# 3_3V_to_1_0V.net
KiCad netlist of a schematic drawn in Altium Designer
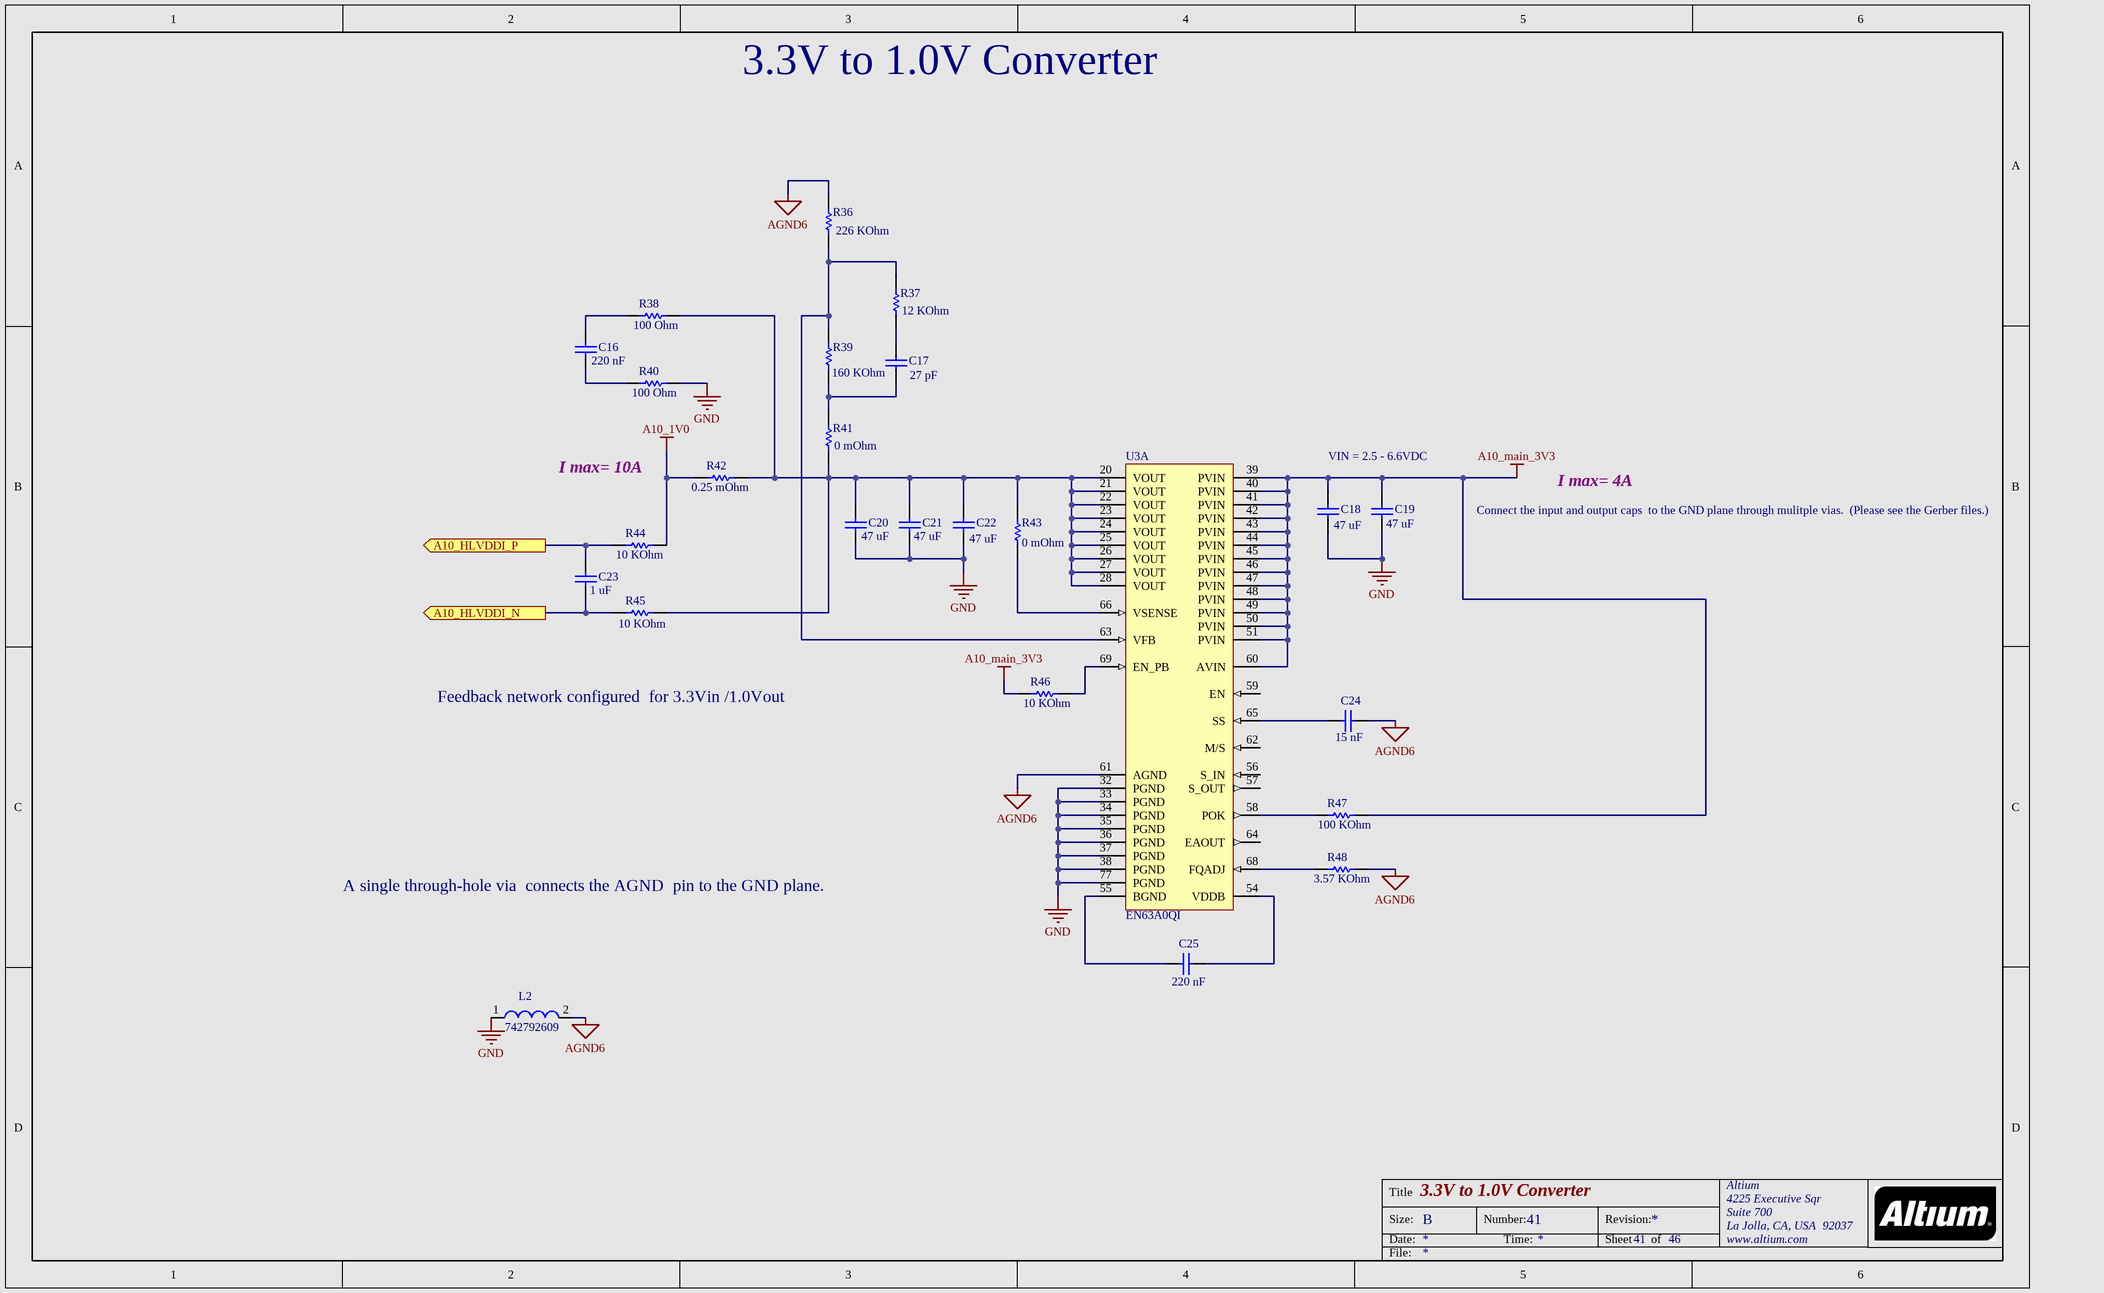
[diagram p0: 3.3V_to_1.0V.SchDoc]

(export (version "E")
  (design (tool "Eeschema 10.0.6"))
  (components
    (comp (ref "C16")
      (value "GRM155R61A224KE19D")
      (footprint "CAPC1005X55X25NL05T10")
      (description "Chip Capacitor, 220 nF, +/- 10%, 10 V, -55 to 85 degC, 0402 (1005 Metric), RoHS, Tape and Reel")
      (fields
        (field (name "TOLERANCE") "10%")
        (field (name "CAPACITANCE") "220 nF")
        (field (name "MANUFACTURER") "Basic Passives")
      )
      (libsource (lib "Altium Content Vault") (part "CAP-NP-2"))
    )
    (comp (ref "C17")
      (value "ECJ-0EC1H270J")
      (footprint "CAPC1005X55X20ML5T10")
      (description "Chip Capacitor, 27 pF, +/- 5%, 50 V, -55 to 125 degC, 0402 (1005 Metric), RoHS, Tape and Reel")
      (fields (field (name "TOLERANCE") "5%") (field (name "CAPACITANCE") "27 pF"))
      (libsource (lib "Altium Content Vault") (part "CMP-1665-00021-1"))
    )
    (comp (ref "C18")
      (value "C3216X5R1A476M160AB")
      (footprint "CAPC3216X180X20ML20")
      (description "Chip Capacitor, 47 uF, +/- 20%, 10 V, -55 to 85 degC, 1206 (3216 Metric), RoHS, Tape and Reel")
      (fields (field (name "TOLERANCE") "20%") (field (name "CAPACITANCE") "47 uF"))
      (libsource (lib "") (part "CAP-NP-2_1"))
    )
    (comp (ref "C19")
      (value "C3216X5R1A476M160AB")
      (footprint "CAPC3216X180X20ML20")
      (description "Chip Capacitor, 47 uF, +/- 20%, 10 V, -55 to 85 degC, 1206 (3216 Metric), RoHS, Tape and Reel")
      (fields (field (name "TOLERANCE") "20%") (field (name "CAPACITANCE") "47 uF"))
      (libsource (lib "") (part "CAP-NP-2_1"))
    )
    (comp (ref "C20")
      (value "C3216X5R1A476M160AB")
      (footprint "CAPC3216X180X20ML20")
      (description "Chip Capacitor, 47 uF, +/- 20%, 10 V, -55 to 85 degC, 1206 (3216 Metric), RoHS, Tape and Reel")
      (fields (field (name "TOLERANCE") "20%") (field (name "CAPACITANCE") "47 uF"))
      (libsource (lib "") (part "CAP-NP-2_1"))
    )
    (comp (ref "C21")
      (value "C3216X5R1A476M160AB")
      (footprint "CAPC3216X180X20ML20")
      (description "Chip Capacitor, 47 uF, +/- 20%, 10 V, -55 to 85 degC, 1206 (3216 Metric), RoHS, Tape and Reel")
      (fields (field (name "TOLERANCE") "20%") (field (name "CAPACITANCE") "47 uF"))
      (libsource (lib "") (part "CAP-NP-2_1"))
    )
    (comp (ref "C22")
      (value "C3216X5R1A476M160AB")
      (footprint "CAPC3216X180X20ML20")
      (description "Chip Capacitor, 47 uF, +/- 20%, 10 V, -55 to 85 degC, 1206 (3216 Metric), RoHS, Tape and Reel")
      (fields (field (name "TOLERANCE") "20%") (field (name "CAPACITANCE") "47 uF"))
      (libsource (lib "") (part "CAP-NP-2_1"))
    )
    (comp (ref "C23")
      (value "CGB2A1X5R1E105K033BC")
      (footprint "CAPC1005X33X10LL5")
      (description "Chip Capacitor, 1 uF, +/- 10%, 25 V, -55 to 85 degC, 0402 (1005 Metric), RoHS, Tape and Reel")
      (fields (field (name "TOLERANCE") "10%") (field (name "CAPACITANCE") "1 uF"))
      (libsource (lib "") (part "CAP-NP-2_1"))
    )
    (comp (ref "C24")
      (value "VJ0402Y153JXQPW1BC")
      (footprint "CAPC1005X55X23ML05T8")
      (description "Chip Capacitor, 15 nF, +/- 5%, 10 V, -55 to 125 degC, 0402 (1005 Metric), RoHS, Tape and Reel")
      (fields (field (name "CAPACITANCE") "15 nF") (field (name "TOLERANCE") "5%"))
      (libsource (lib "Altium Content Vault") (part "CAP-NP-2"))
    )
    (comp (ref "C25")
      (value "GRM155R61A224KE19D")
      (footprint "CAPC1005X55X25NL05T10")
      (description "Chip Capacitor, 220 nF, +/- 10%, 10 V, -55 to 85 degC, 0402 (1005 Metric), RoHS, Tape and Reel")
      (fields
        (field (name "TOLERANCE") "10%")
        (field (name "CAPACITANCE") "220 nF")
        (field (name "MANUFACTURER") "Basic Passives")
      )
      (libsource (lib "Altium Content Vault") (part "CAP-NP-2"))
    )
    (comp (ref "L2")
      (value "742792609")
      (footprint "SMD-0603")
      (description "SMD EMI Suppression Ferrite Bead WE-CBF, Z = 30 Ohm")
      (libsource (lib "Altium Content Vault") (part "CMP-0220-00193-1"))
    )
    (comp (ref "R36")
      (value "ERJ-2RKF2263X")
      (footprint "RESC1005X40X25NL05T05")
      (description "Chip Resistor, 226 KOhm, +/- 1%, 100 mW, -55 to 155 degC, 0402 (1005 Metric), RoHS, Tape and Reel")
      (fields
        (field (name "RESISTANCE") "226 KOhm")
        (field (name "TOLERANCE") "1%")
        (field (name "MANUFACTURER") "Basic Passives")
      )
      (libsource (lib "Altium Content Vault") (part "RES-2"))
    )
    (comp (ref "R37")
      (value "ERJ-2RKF1202X")
      (footprint "RESC1005X40X25ML05T05")
      (description "Chip Resistor, 12 KOhm, +/- 1%, 0.1 W, -55 to 155 degC, 0402 (1005 Metric), RoHS, Tape and Reel")
      (fields (field (name "RESISTANCE") "12 KOhm") (field (name "TOLERANCE") "1%"))
      (libsource (lib "Altium Content Vault") (part "RES-2"))
    )
    (comp (ref "R38")
      (value "ERJ-2RKF1000X")
      (footprint "RESC1005X40X25LL05T05")
      (description "Chip Resistor, 100 Ohm, +/- 1%, 100 mW, -55 to 155 degC, 0402 (1005 Metric), RoHS, Tape and Reel")
      (fields
        (field (name "TOLERANCE") "1%")
        (field (name "RESISTANCE") "100 Ohm")
        (field (name "MANUFACTURER") "Basic Passives")
      )
      (libsource (lib "Altium Content Vault") (part "RES-2"))
    )
    (comp (ref "R39")
      (value "CRCW0402160KFKED")
      (footprint "RESC1005X40X25ML05T05")
      (description "Chip Resistor, 160 KOhm, +/- 1%, 63 mW, -55 to 155 degC, 0402 (1005 Metric), RoHS, Tape and Reel")
      (fields
        (field (name "TOLERANCE") "1%")
        (field (name "RESISTANCE") "160 KOhm")
        (field (name "MANUFACTURER") "Basic Passives")
      )
      (libsource (lib "Altium Content Vault") (part "RES-2"))
    )
    (comp (ref "R40")
      (value "ERJ-2RKF1000X")
      (footprint "RESC1005X40X25LL05T05")
      (description "Chip Resistor, 100 Ohm, +/- 1%, 100 mW, -55 to 155 degC, 0402 (1005 Metric), RoHS, Tape and Reel")
      (fields
        (field (name "TOLERANCE") "1%")
        (field (name "RESISTANCE") "100 Ohm")
        (field (name "MANUFACTURER") "Basic Passives")
      )
      (libsource (lib "Altium Content Vault") (part "RES-2"))
    )
    (comp (ref "R41")
      (value "ERJ-2GE0R00X")
      (footprint "RESC1005X40X25ML05T05")
      (description "Chip Resistor, 0 mOhm, +/- 5%, 100 mW, -55 to 155 degC, 0402 (1005 Metric), RoHS, Tape and Reel")
      (fields
        (field (name "TOLERANCE") "5%")
        (field (name "RESISTANCE") "0 mOhm")
        (field (name "MANUFACTURER") "Basic Passives")
      )
      (libsource (lib "Altium Content Vault") (part "RES-2"))
    )
    (comp (ref "R42")
      (value "CSS2725FTL250")
      (footprint "STAC-CSS2725-099H_V")
      (description "Chip Resistor, 0.25 mOhm, +/- 1%, 4 W, -55 to 225 degC, 2725 (6865 Metric), RoHS, Tape and Reel")
      (fields (field (name "TOLERANCE") "1%") (field (name "RESISTANCE") "0.25 mOhm"))
      (libsource (lib "Altium Content Vault") (part "RES-2"))
    )
    (comp (ref "R43")
      (value "ERJ-2GE0R00X")
      (footprint "RESC1005X40X25ML05T05")
      (description "Chip Resistor, 0 mOhm, +/- 5%, 100 mW, -55 to 155 degC, 0402 (1005 Metric), RoHS, Tape and Reel")
      (fields
        (field (name "TOLERANCE") "5%")
        (field (name "RESISTANCE") "0 mOhm")
        (field (name "MANUFACTURER") "Basic Passives")
      )
      (libsource (lib "Altium Content Vault") (part "RES-2"))
    )
    (comp (ref "R44")
      (value "ERJ-2RKF1002X")
      (footprint "RESC1005X40X25NL05T05")
      (description "Chip Resistor, 10 KOhm, +/- 1%, 100 mW, -55 to 155 degC, 0402 (1005 Metric), RoHS, Tape and Reel")
      (fields
        (field (name "TOLERANCE") "1%")
        (field (name "RESISTANCE") "10 KOhm")
        (field (name "MANUFACTURER") "Basic Passives")
      )
      (libsource (lib "Altium Content Vault") (part "RES-2"))
    )
    (comp (ref "R45")
      (value "ERJ-2RKF1002X")
      (footprint "RESC1005X40X25NL05T05")
      (description "Chip Resistor, 10 KOhm, +/- 1%, 100 mW, -55 to 155 degC, 0402 (1005 Metric), RoHS, Tape and Reel")
      (fields
        (field (name "TOLERANCE") "1%")
        (field (name "RESISTANCE") "10 KOhm")
        (field (name "MANUFACTURER") "Basic Passives")
      )
      (libsource (lib "Altium Content Vault") (part "RES-2"))
    )
    (comp (ref "R46")
      (value "ERJ-2RKF1002X")
      (footprint "RESC1005X40X25NL05T05")
      (description "Chip Resistor, 10 KOhm, +/- 1%, 100 mW, -55 to 155 degC, 0402 (1005 Metric), RoHS, Tape and Reel")
      (fields
        (field (name "TOLERANCE") "1%")
        (field (name "RESISTANCE") "10 KOhm")
        (field (name "MANUFACTURER") "Basic Passives")
      )
      (libsource (lib "Altium Content Vault") (part "RES-2"))
    )
    (comp (ref "R47")
      (value "ERJ-2RKF1003X")
      (footprint "RESC1005X40X25LL05T05")
      (description "Chip Resistor, 100 KOhm, +/- 1%, 100 mW, -55 to 155 degC, 0402 (1005 Metric), RoHS, Tape and Reel")
      (fields
        (field (name "RESISTANCE") "100 KOhm")
        (field (name "TOLERANCE") "1%")
        (field (name "MANUFACTURER") "Basic Passives")
      )
      (libsource (lib "Altium Content Vault") (part "RES-2"))
    )
    (comp (ref "R48")
      (value "CRCW04023K57FKED")
      (footprint "RESC1005X40X25NL05T05")
      (description "Chip Resistor, 3.57 KOhm, +/- 1%, 63 mW, -55 to 155 degC, 0402 (1005 Metric), RoHS, Tape and Reel")
      (fields (field (name "RESISTANCE") "3.57 KOhm") (field (name "TOLERANCE") "1%"))
      (libsource (lib "Altium Content Vault") (part "RES"))
    )
    (comp (ref "U3")
      (value "EN63A0QI")
      (footprint "ALTR-QFN-76_A-305_V")
      (libsource (lib "Altium Content Vault") (part "ALTR-EN63A0QX-QFN76"))
    )
  )
  (nets
    (net (code "1") (name "/A10_HLVDDI_N") (class "Default")
      (node (ref "C23") (pin "1") (pinfunction "1_1") (pintype "passive"))
      (node (ref "R45") (pin "1") (pinfunction "1_1") (pintype "passive"))
    )
    (net (code "2") (name "/A10_HLVDDI_P") (class "Default")
      (node (ref "C23") (pin "2") (pinfunction "2_2") (pintype "passive"))
      (node (ref "R44") (pin "1") (pinfunction "1_1") (pintype "passive"))
    )
    (net (code "3") (name "A10_1V0") (class "Default")
      (node (ref "R42") (pin "1") (pinfunction "1_1") (pintype "passive"))
      (node (ref "R44") (pin "2") (pinfunction "2_2") (pintype "passive"))
    )
    (net (code "4") (name "A10_main_3V3") (class "Default")
      (node (ref "C18") (pin "2") (pinfunction "2_2") (pintype "passive"))
      (node (ref "C19") (pin "2") (pinfunction "2_2") (pintype "passive"))
      (node (ref "R46") (pin "1") (pinfunction "1_1") (pintype "passive"))
      (node (ref "R47") (pin "2") (pinfunction "2_2") (pintype "passive"))
      (node (ref "U3") (pin "39") (pinfunction "PVIN_39") (pintype "power_in"))
      (node (ref "U3") (pin "40") (pinfunction "PVIN_40") (pintype "power_in"))
      (node (ref "U3") (pin "41") (pinfunction "PVIN_41") (pintype "power_in"))
      (node (ref "U3") (pin "42") (pinfunction "PVIN_42") (pintype "power_in"))
      (node (ref "U3") (pin "43") (pinfunction "PVIN_43") (pintype "power_in"))
      (node (ref "U3") (pin "44") (pinfunction "PVIN_44") (pintype "power_in"))
      (node (ref "U3") (pin "45") (pinfunction "PVIN_45") (pintype "power_in"))
      (node (ref "U3") (pin "46") (pinfunction "PVIN_46") (pintype "power_in"))
      (node (ref "U3") (pin "47") (pinfunction "PVIN_47") (pintype "power_in"))
      (node (ref "U3") (pin "48") (pinfunction "PVIN_48") (pintype "power_in"))
      (node (ref "U3") (pin "49") (pinfunction "PVIN_49") (pintype "power_in"))
      (node (ref "U3") (pin "50") (pinfunction "PVIN_50") (pintype "power_in"))
      (node (ref "U3") (pin "51") (pinfunction "PVIN_51") (pintype "power_in"))
      (node (ref "U3") (pin "60") (pinfunction "AVIN_60") (pintype "power_in"))
    )
    (net (code "5") (name "AGND6") (class "Default")
      (node (ref "C24") (pin "1") (pinfunction "1_1") (pintype "passive"))
      (node (ref "L2") (pin "2") (pinfunction "2_2") (pintype "passive"))
      (node (ref "R36") (pin "2") (pinfunction "2_2") (pintype "passive"))
      (node (ref "R48") (pin "2") (pinfunction "2_2") (pintype "passive"))
      (node (ref "U3") (pin "61") (pinfunction "AGND_61") (pintype "power_in"))
    )
    (net (code "6") (name "GND") (class "Default")
      (node (ref "C18") (pin "1") (pinfunction "1_1") (pintype "passive"))
      (node (ref "C19") (pin "1") (pinfunction "1_1") (pintype "passive"))
      (node (ref "C20") (pin "1") (pinfunction "1_1") (pintype "passive"))
      (node (ref "C21") (pin "1") (pinfunction "1_1") (pintype "passive"))
      (node (ref "C22") (pin "1") (pinfunction "1_1") (pintype "passive"))
      (node (ref "L2") (pin "1") (pinfunction "1_1") (pintype "passive"))
      (node (ref "R40") (pin "1") (pinfunction "1_1") (pintype "passive"))
      (node (ref "U3") (pin "32") (pinfunction "PGND_32") (pintype "power_in"))
      (node (ref "U3") (pin "33") (pinfunction "PGND_33") (pintype "power_in"))
      (node (ref "U3") (pin "34") (pinfunction "PGND_34") (pintype "power_in"))
      (node (ref "U3") (pin "35") (pinfunction "PGND_35") (pintype "power_in"))
      (node (ref "U3") (pin "36") (pinfunction "PGND_36") (pintype "power_in"))
      (node (ref "U3") (pin "37") (pinfunction "PGND_37") (pintype "power_in"))
      (node (ref "U3") (pin "38") (pinfunction "PGND_38") (pintype "power_in"))
      (node (ref "U3") (pin "77") (pinfunction "PGND_77") (pintype "power_in"))
    )
    (net (code "7") (name "Net-(C16-Pad1)") (class "Default")
      (node (ref "C16") (pin "1") (pinfunction "1_1") (pintype "passive"))
      (node (ref "R38") (pin "2") (pinfunction "2_2") (pintype "passive"))
    )
    (net (code "8") (name "Net-(C16-Pad2)") (class "Default")
      (node (ref "C16") (pin "2") (pinfunction "2_2") (pintype "passive"))
      (node (ref "R40") (pin "2") (pinfunction "2_2") (pintype "passive"))
    )
    (net (code "9") (name "Net-(C17-Pad1)") (class "Default")
      (node (ref "C17") (pin "1") (pinfunction "1_1") (pintype "passive"))
      (node (ref "R39") (pin "1") (pinfunction "1_1") (pintype "passive"))
      (node (ref "R41") (pin "2") (pinfunction "2_2") (pintype "passive"))
    )
    (net (code "10") (name "Net-(C17-Pad2)") (class "Default")
      (node (ref "C17") (pin "2") (pinfunction "2_2") (pintype "passive"))
      (node (ref "R37") (pin "1") (pinfunction "1_1") (pintype "passive"))
    )
    (net (code "11") (name "Net-(C20-Pad2)") (class "Default")
      (node (ref "C20") (pin "2") (pinfunction "2_2") (pintype "passive"))
      (node (ref "C21") (pin "2") (pinfunction "2_2") (pintype "passive"))
      (node (ref "C22") (pin "2") (pinfunction "2_2") (pintype "passive"))
      (node (ref "R38") (pin "1") (pinfunction "1_1") (pintype "passive"))
      (node (ref "R41") (pin "1") (pinfunction "1_1") (pintype "passive"))
      (node (ref "R42") (pin "2") (pinfunction "2_2") (pintype "passive"))
      (node (ref "R43") (pin "2") (pinfunction "2_2") (pintype "passive"))
      (node (ref "R45") (pin "2") (pinfunction "2_2") (pintype "passive"))
      (node (ref "U3") (pin "20") (pinfunction "VOUT_20") (pintype "power_in"))
      (node (ref "U3") (pin "21") (pinfunction "VOUT_21") (pintype "power_in"))
      (node (ref "U3") (pin "22") (pinfunction "VOUT_22") (pintype "power_in"))
      (node (ref "U3") (pin "23") (pinfunction "VOUT_23") (pintype "power_in"))
      (node (ref "U3") (pin "24") (pinfunction "VOUT_24") (pintype "power_in"))
      (node (ref "U3") (pin "25") (pinfunction "VOUT_25") (pintype "power_in"))
      (node (ref "U3") (pin "26") (pinfunction "VOUT_26") (pintype "power_in"))
      (node (ref "U3") (pin "27") (pinfunction "VOUT_27") (pintype "power_in"))
      (node (ref "U3") (pin "28") (pinfunction "VOUT_28") (pintype "power_in"))
    )
    (net (code "12") (name "Net-(U3A-BGND)") (class "Default")
      (node (ref "C25") (pin "1") (pinfunction "1_1") (pintype "passive"))
      (node (ref "U3") (pin "55") (pinfunction "BGND_55") (pintype "power_in"))
    )
    (net (code "13") (name "Net-(U3A-EN_PB)") (class "Default")
      (node (ref "R46") (pin "2") (pinfunction "2_2") (pintype "passive"))
      (node (ref "U3") (pin "69") (pinfunction "EN_PB_69") (pintype "input"))
    )
    (net (code "14") (name "Net-(U3A-FQADJ)") (class "Default")
      (node (ref "R48") (pin "1") (pinfunction "1_1") (pintype "passive"))
      (node (ref "U3") (pin "68") (pinfunction "FQADJ_68") (pintype "input"))
    )
    (net (code "15") (name "Net-(U3A-POK)") (class "Default")
      (node (ref "R47") (pin "1") (pinfunction "1_1") (pintype "passive"))
      (node (ref "U3") (pin "58") (pinfunction "POK_58") (pintype "output"))
    )
    (net (code "16") (name "Net-(U3A-SS)") (class "Default")
      (node (ref "C24") (pin "2") (pinfunction "2_2") (pintype "passive"))
      (node (ref "U3") (pin "65") (pinfunction "SS_65") (pintype "input"))
    )
    (net (code "17") (name "Net-(U3A-VDDB)") (class "Default")
      (node (ref "C25") (pin "2") (pinfunction "2_2") (pintype "passive"))
      (node (ref "U3") (pin "54") (pinfunction "VDDB_54") (pintype "power_in"))
    )
    (net (code "18") (name "Net-(U3A-VFB)") (class "Default")
      (node (ref "R36") (pin "1") (pinfunction "1_1") (pintype "passive"))
      (node (ref "R37") (pin "2") (pinfunction "2_2") (pintype "passive"))
      (node (ref "R39") (pin "2") (pinfunction "2_2") (pintype "passive"))
      (node (ref "U3") (pin "63") (pinfunction "VFB_63") (pintype "input"))
    )
    (net (code "19") (name "Net-(U3A-VSENSE)") (class "Default")
      (node (ref "R43") (pin "1") (pinfunction "1_1") (pintype "passive"))
      (node (ref "U3") (pin "66") (pinfunction "VSENSE_66") (pintype "input"))
    )
    (net (code "20") (name "unconnected-(U3A-EAOUT-Pad64)") (class "Default")
      (node (ref "U3") (pin "64") (pinfunction "EAOUT_64") (pintype "output"))
    )
    (net (code "21") (name "unconnected-(U3A-EN-Pad59)") (class "Default")
      (node (ref "U3") (pin "59") (pinfunction "EN_59") (pintype "input"))
    )
    (net (code "22") (name "unconnected-(U3A-M{slash}S-Pad62)") (class "Default")
      (node (ref "U3") (pin "62") (pinfunction "M/S_62") (pintype "input"))
    )
    (net (code "23") (name "unconnected-(U3A-S_IN-Pad56)") (class "Default")
      (node (ref "U3") (pin "56") (pinfunction "S_IN_56") (pintype "input"))
    )
    (net (code "24") (name "unconnected-(U3A-S_OUT-Pad57)") (class "Default")
      (node (ref "U3") (pin "57") (pinfunction "S_OUT_57") (pintype "output"))
    )
  )
)
